# AudioAmplifierExample.net
KiCad netlist of a schematic drawn in EAGLE
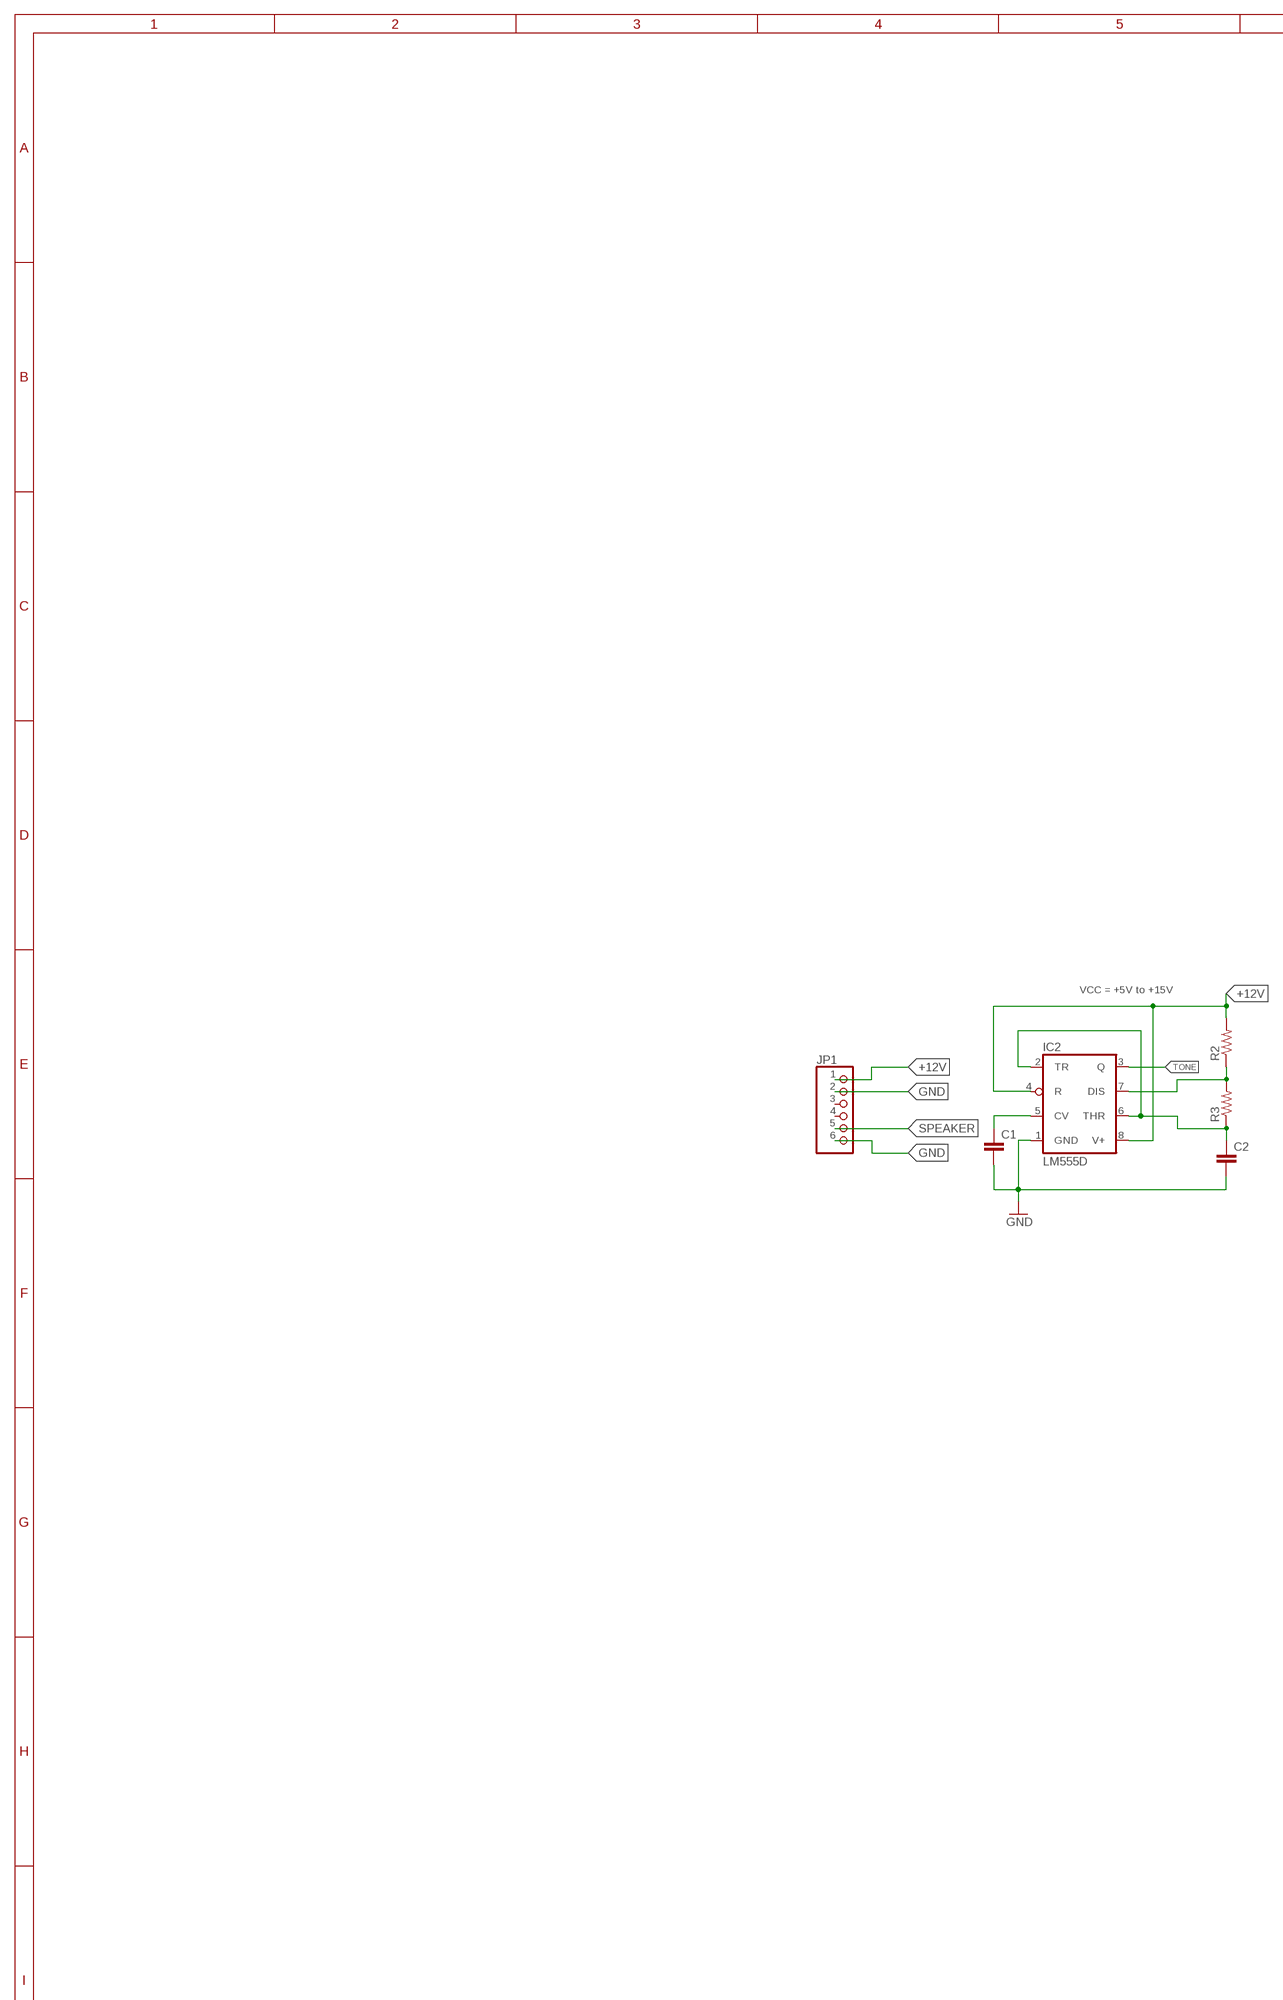
[diagram p0: schematic, sheet 1, part 1 of 2]
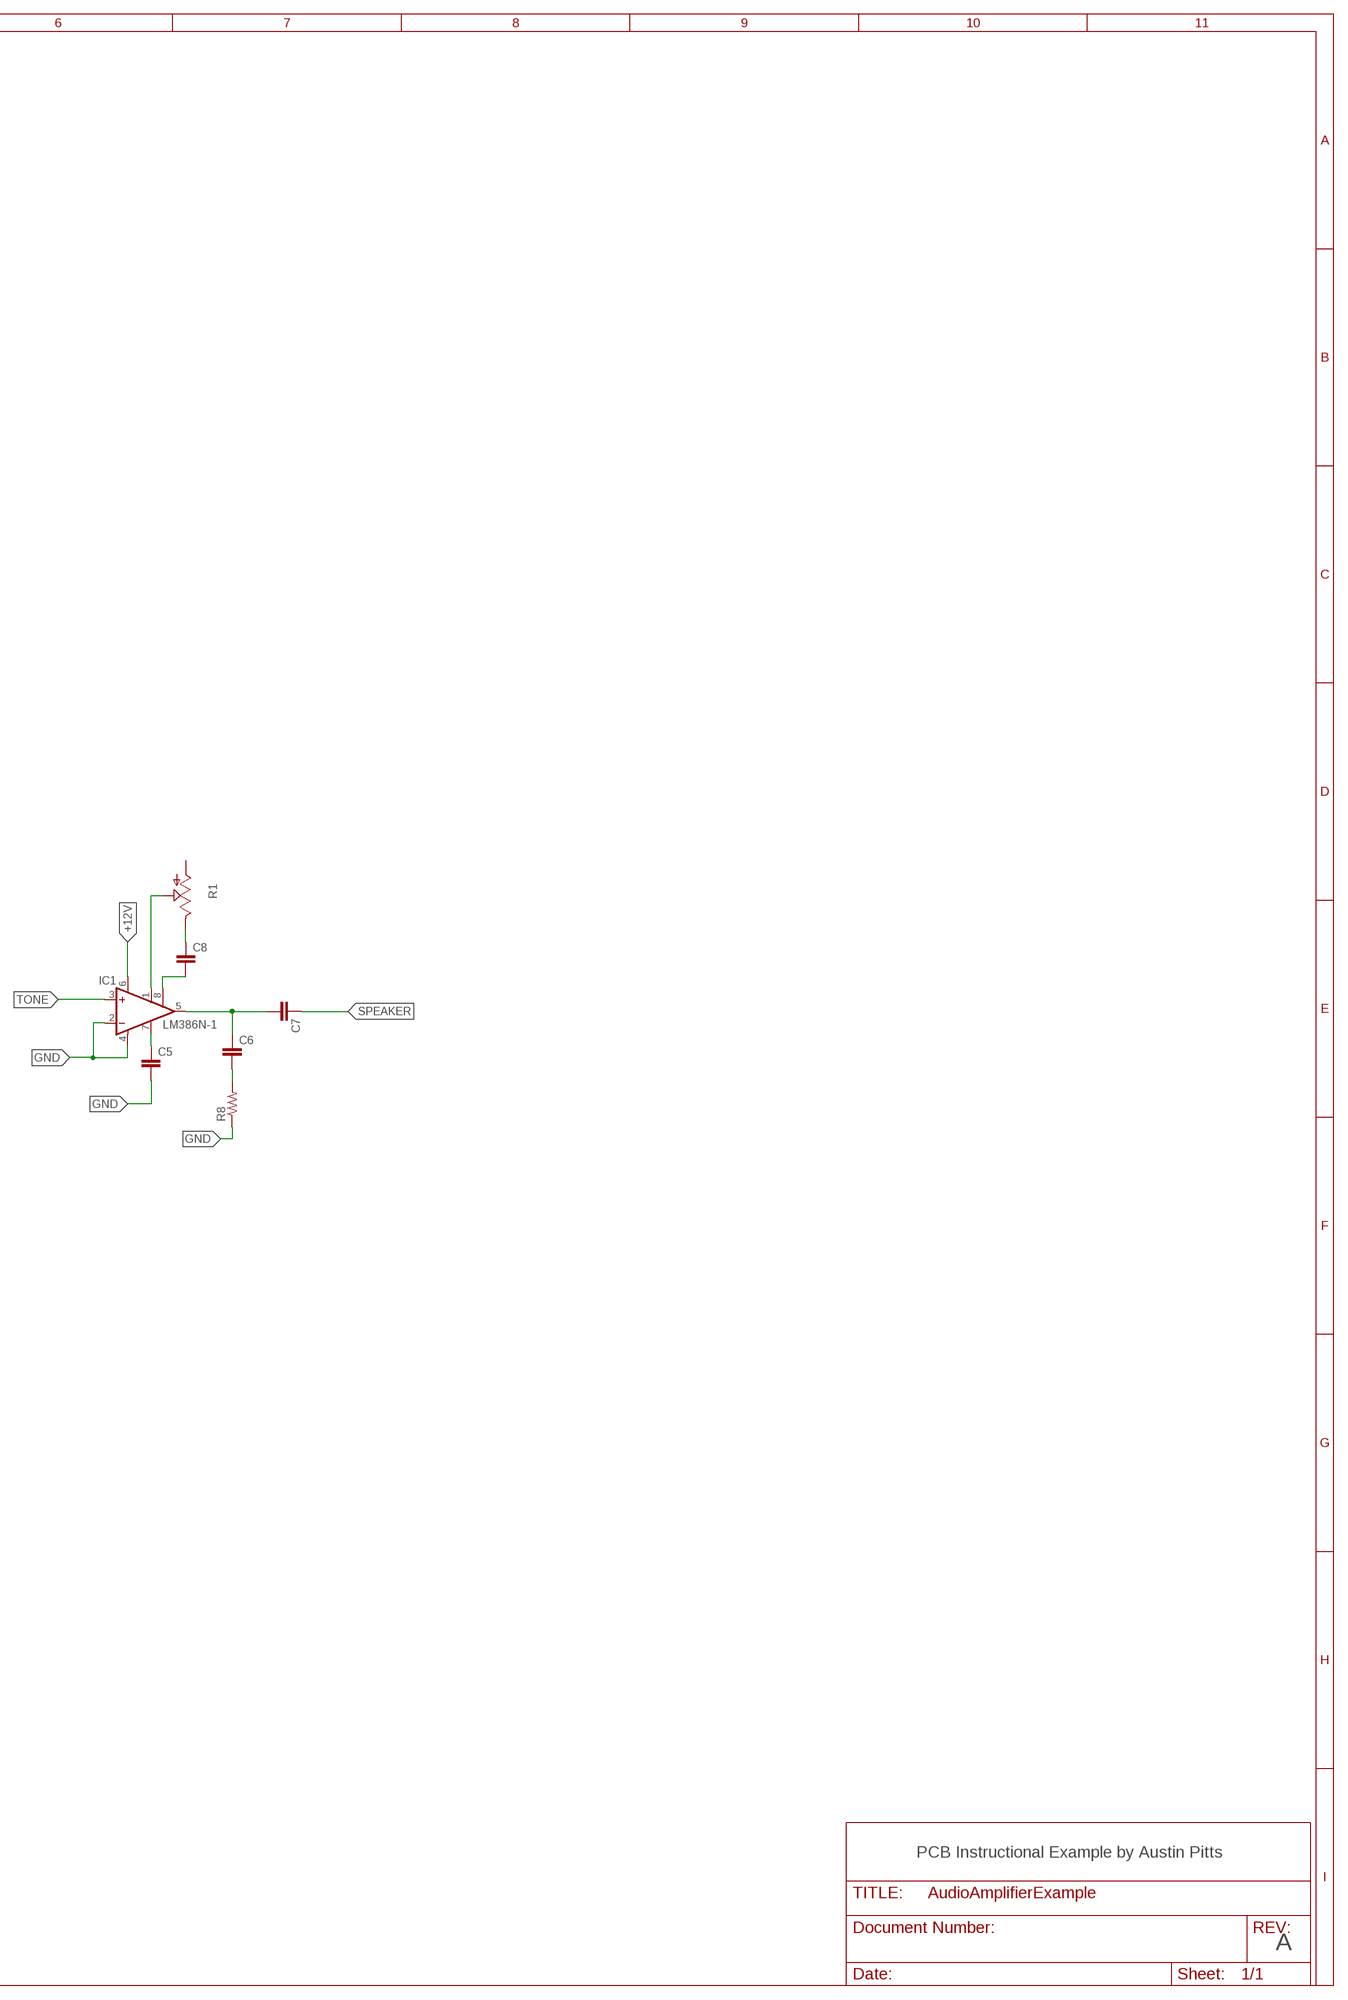
[diagram p1: schematic, sheet 1, part 2 of 2]

(export (version "E")
  (design (tool "Eeschema 10.0.6"))
  (components
    (comp (ref "C1")
      (value "C2,5-3")
      (footprint "eagle-import:C2.5-3")
      (libsource (lib "eagle-import") (part "C2,5-3"))
    )
    (comp (ref "C2")
      (value "C2,5-3")
      (footprint "eagle-import:C2.5-3")
      (libsource (lib "eagle-import") (part "C2,5-3"))
    )
    (comp (ref "C5")
      (value "C2,5-3")
      (footprint "eagle-import:C2.5-3")
      (libsource (lib "eagle-import") (part "C2,5-3"))
    )
    (comp (ref "C6")
      (value "C2,5-3")
      (footprint "eagle-import:C2.5-3")
      (libsource (lib "eagle-import") (part "C2,5-3"))
    )
    (comp (ref "C7")
      (value "C2,5-3")
      (footprint "eagle-import:C2.5-3")
      (libsource (lib "eagle-import") (part "C2,5-3"))
    )
    (comp (ref "C8")
      (value "C2,5-3")
      (footprint "eagle-import:C2.5-3")
      (libsource (lib "eagle-import") (part "C2,5-3"))
    )
    (comp (ref "IC1")
      (value "LM386N-1")
      (footprint "eagle-import:DIL08@1")
      (libsource (lib "eagle-import") (part "LM386?-N1"))
    )
    (comp (ref "IC2")
      (value "LM555D")
      (footprint "eagle-import:SO08")
      (libsource (lib "eagle-import") (part "555DLM"))
    )
    (comp (ref "JP1")
      (value "PINHD-1X6")
      (footprint "eagle-import:1X06")
      (libsource (lib "eagle-import") (part "PINHD-1X6"))
    )
    (comp (ref "R1")
      (value "TRIM_US-B25P")
      (footprint "eagle-import:B25P")
      (libsource (lib "eagle-import") (part "TRIM_US-B25P"))
    )
    (comp (ref "R2")
      (value "R-US_0207/7")
      (footprint "eagle-import:0207_7")
      (libsource (lib "eagle-import") (part "R-US_0207/7"))
    )
    (comp (ref "R3")
      (value "R-US_0207/7")
      (footprint "eagle-import:0207_7")
      (libsource (lib "eagle-import") (part "R-US_0207/7"))
    )
    (comp (ref "R8")
      (value "R-US_0207/7")
      (footprint "eagle-import:0207_7")
      (libsource (lib "eagle-import") (part "R-US_0207/7"))
    )
  )
  (nets
    (net (code "1") (name "+12V") (class "Default")
      (node (ref "IC1") (pin "6") (pinfunction "VS_6") (pintype "power_in"))
      (node (ref "IC2") (pin "4") (pinfunction "R_4") (pintype "input"))
      (node (ref "IC2") (pin "8") (pinfunction "V+_8") (pintype "power_in"))
      (node (ref "JP1") (pin "1") (pinfunction "1_1") (pintype "passive"))
      (node (ref "R2") (pin "2") (pinfunction "2_2") (pintype "passive"))
    )
    (net (code "2") (name "GND") (class "Default")
      (node (ref "C1") (pin "2") (pinfunction "2_2") (pintype "passive"))
      (node (ref "C2") (pin "2") (pinfunction "2_2") (pintype "passive"))
      (node (ref "C5") (pin "2") (pinfunction "2_2") (pintype "passive"))
      (node (ref "IC1") (pin "2") (pinfunction "-IN_2") (pintype "input"))
      (node (ref "IC1") (pin "4") (pinfunction "GND_4") (pintype "power_in"))
      (node (ref "IC2") (pin "1") (pinfunction "GND_1") (pintype "power_in"))
      (node (ref "JP1") (pin "2") (pinfunction "2_2") (pintype "passive"))
      (node (ref "JP1") (pin "6") (pinfunction "6_6") (pintype "passive"))
      (node (ref "R8") (pin "1") (pinfunction "1_1") (pintype "passive"))
    )
    (net (code "3") (name "Net-(C6-Pad2)") (class "Default")
      (node (ref "C6") (pin "2") (pinfunction "2_2") (pintype "passive"))
      (node (ref "R8") (pin "2") (pinfunction "2_2") (pintype "passive"))
    )
    (net (code "4") (name "Net-(C8-Pad1)") (class "Default")
      (node (ref "C8") (pin "1") (pinfunction "1_1") (pintype "passive"))
      (node (ref "R1") (pin "E") (pinfunction "E_E") (pintype "passive"))
    )
    (net (code "5") (name "Net-(C8-Pad2)") (class "Default")
      (node (ref "C8") (pin "2") (pinfunction "2_2") (pintype "passive"))
      (node (ref "IC1") (pin "8") (pinfunction "GAIN_8") (pintype "passive"))
    )
    (net (code "6") (name "Net-(IC1-BYPASS)") (class "Default")
      (node (ref "C5") (pin "1") (pinfunction "1_1") (pintype "passive"))
      (node (ref "IC1") (pin "7") (pinfunction "BYPASS_7") (pintype "passive"))
    )
    (net (code "7") (name "Net-(IC1-GAIN-Pad1)") (class "Default")
      (node (ref "IC1") (pin "1") (pinfunction "GAIN_1") (pintype "passive"))
      (node (ref "R1") (pin "S") (pinfunction "S_S") (pintype "passive"))
    )
    (net (code "8") (name "Net-(IC1-OUT)") (class "Default")
      (node (ref "C6") (pin "1") (pinfunction "1_1") (pintype "passive"))
      (node (ref "C7") (pin "2") (pinfunction "2_2") (pintype "passive"))
      (node (ref "IC1") (pin "5") (pinfunction "OUT_5") (pintype "output"))
    )
    (net (code "9") (name "Net-(IC2-CV)") (class "Default")
      (node (ref "C1") (pin "1") (pinfunction "1_1") (pintype "passive"))
      (node (ref "IC2") (pin "5") (pinfunction "CV_5") (pintype "input"))
    )
    (net (code "10") (name "Net-(IC2-DIS)") (class "Default")
      (node (ref "IC2") (pin "7") (pinfunction "DIS_7") (pintype "input"))
      (node (ref "R2") (pin "1") (pinfunction "1_1") (pintype "passive"))
      (node (ref "R3") (pin "2") (pinfunction "2_2") (pintype "passive"))
    )
    (net (code "11") (name "Net-(IC2-THR)") (class "Default")
      (node (ref "C2") (pin "1") (pinfunction "1_1") (pintype "passive"))
      (node (ref "IC2") (pin "2") (pinfunction "TR_2") (pintype "input"))
      (node (ref "IC2") (pin "6") (pinfunction "THR_6") (pintype "input"))
      (node (ref "R3") (pin "1") (pinfunction "1_1") (pintype "passive"))
    )
    (net (code "12") (name "SPEAKER") (class "Default")
      (node (ref "C7") (pin "1") (pinfunction "1_1") (pintype "passive"))
      (node (ref "JP1") (pin "5") (pinfunction "5_5") (pintype "passive"))
    )
    (net (code "13") (name "TONE") (class "Default")
      (node (ref "IC1") (pin "3") (pinfunction "+IN_3") (pintype "input"))
      (node (ref "IC2") (pin "3") (pinfunction "Q_3") (pintype "output"))
    )
    (net (code "14") (name "unconnected-(JP1-Pad3)") (class "Default")
      (node (ref "JP1") (pin "3") (pinfunction "3_3") (pintype "passive"))
    )
    (net (code "15") (name "unconnected-(JP1-Pad4)") (class "Default")
      (node (ref "JP1") (pin "4") (pinfunction "4_4") (pintype "passive"))
    )
    (net (code "16") (name "unconnected-(R1-PadA)") (class "Default")
      (node (ref "R1") (pin "A") (pinfunction "A_A") (pintype "passive"))
    )
  )
)
